# Puzzle_LED.net
KiCad netlist of a schematic drawn in EAGLE
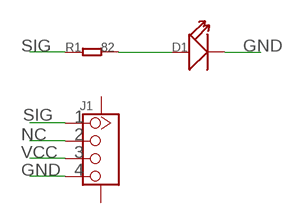
[diagram p0: schematic, sheet 1]

(export (version "E")
  (design (tool "Eeschema 10.0.6"))
  (components
    (comp (ref "D1")
      (value "LED-6MM")
      (footprint "eagle-import:LED-2P-2.54-6MM")
      (libsource (lib "eagle-import") (part "LED-6MM"))
    )
    (comp (ref "J1")
      (value "TWIG-4P-2.0-SMD-FEMALE-REINFORCE'90D'")
      (footprint "eagle-import:4P-SMD-2.0-90D")
      (libsource (lib "eagle-import") (part "TWIG-4P-2.0-SMD-FEMALE-REINFORCE'90D'"))
    )
    (comp (ref "R1")
      (value "82")
      (footprint "eagle-import:0603")
      (libsource (lib "eagle-import") (part "R-0603"))
    )
  )
  (nets
    (net (code "1") (name "/GND") (class "Default")
      (node (ref "D1") (pin "-") (pinfunction "-_-") (pintype "passive"))
      (node (ref "J1") (pin "4") (pinfunction "4_4") (pintype "bidirectional"))
    )
    (net (code "2") (name "/SIG") (class "Default")
      (node (ref "J1") (pin "1") (pinfunction "1_1") (pintype "bidirectional"))
      (node (ref "R1") (pin "1") (pinfunction "1_1") (pintype "passive"))
    )
    (net (code "3") (name "Net-(D1-Pad+)") (class "Default")
      (node (ref "D1") (pin "+") (pinfunction "+_+") (pintype "passive"))
      (node (ref "R1") (pin "2") (pinfunction "2_2") (pintype "passive"))
    )
    (net (code "4") (name "unconnected-(J1-Pad2)") (class "Default")
      (node (ref "J1") (pin "2") (pinfunction "2_2") (pintype "bidirectional"))
    )
    (net (code "5") (name "unconnected-(J1-Pad3)") (class "Default")
      (node (ref "J1") (pin "3") (pinfunction "3_3") (pintype "bidirectional"))
    )
    (net (code "6") (name "unconnected-(J1-PadSS1)") (class "Default")
      (node (ref "J1") (pin "SS1") (pinfunction "SS1_SS1") (pintype "bidirectional"))
    )
    (net (code "7") (name "unconnected-(J1-PadSS2)") (class "Default")
      (node (ref "J1") (pin "SS2") (pinfunction "SS2_SS2") (pintype "bidirectional"))
    )
  )
)
